# Rainbow.net
KiCad netlist of a schematic drawn in EasyEDA Pro
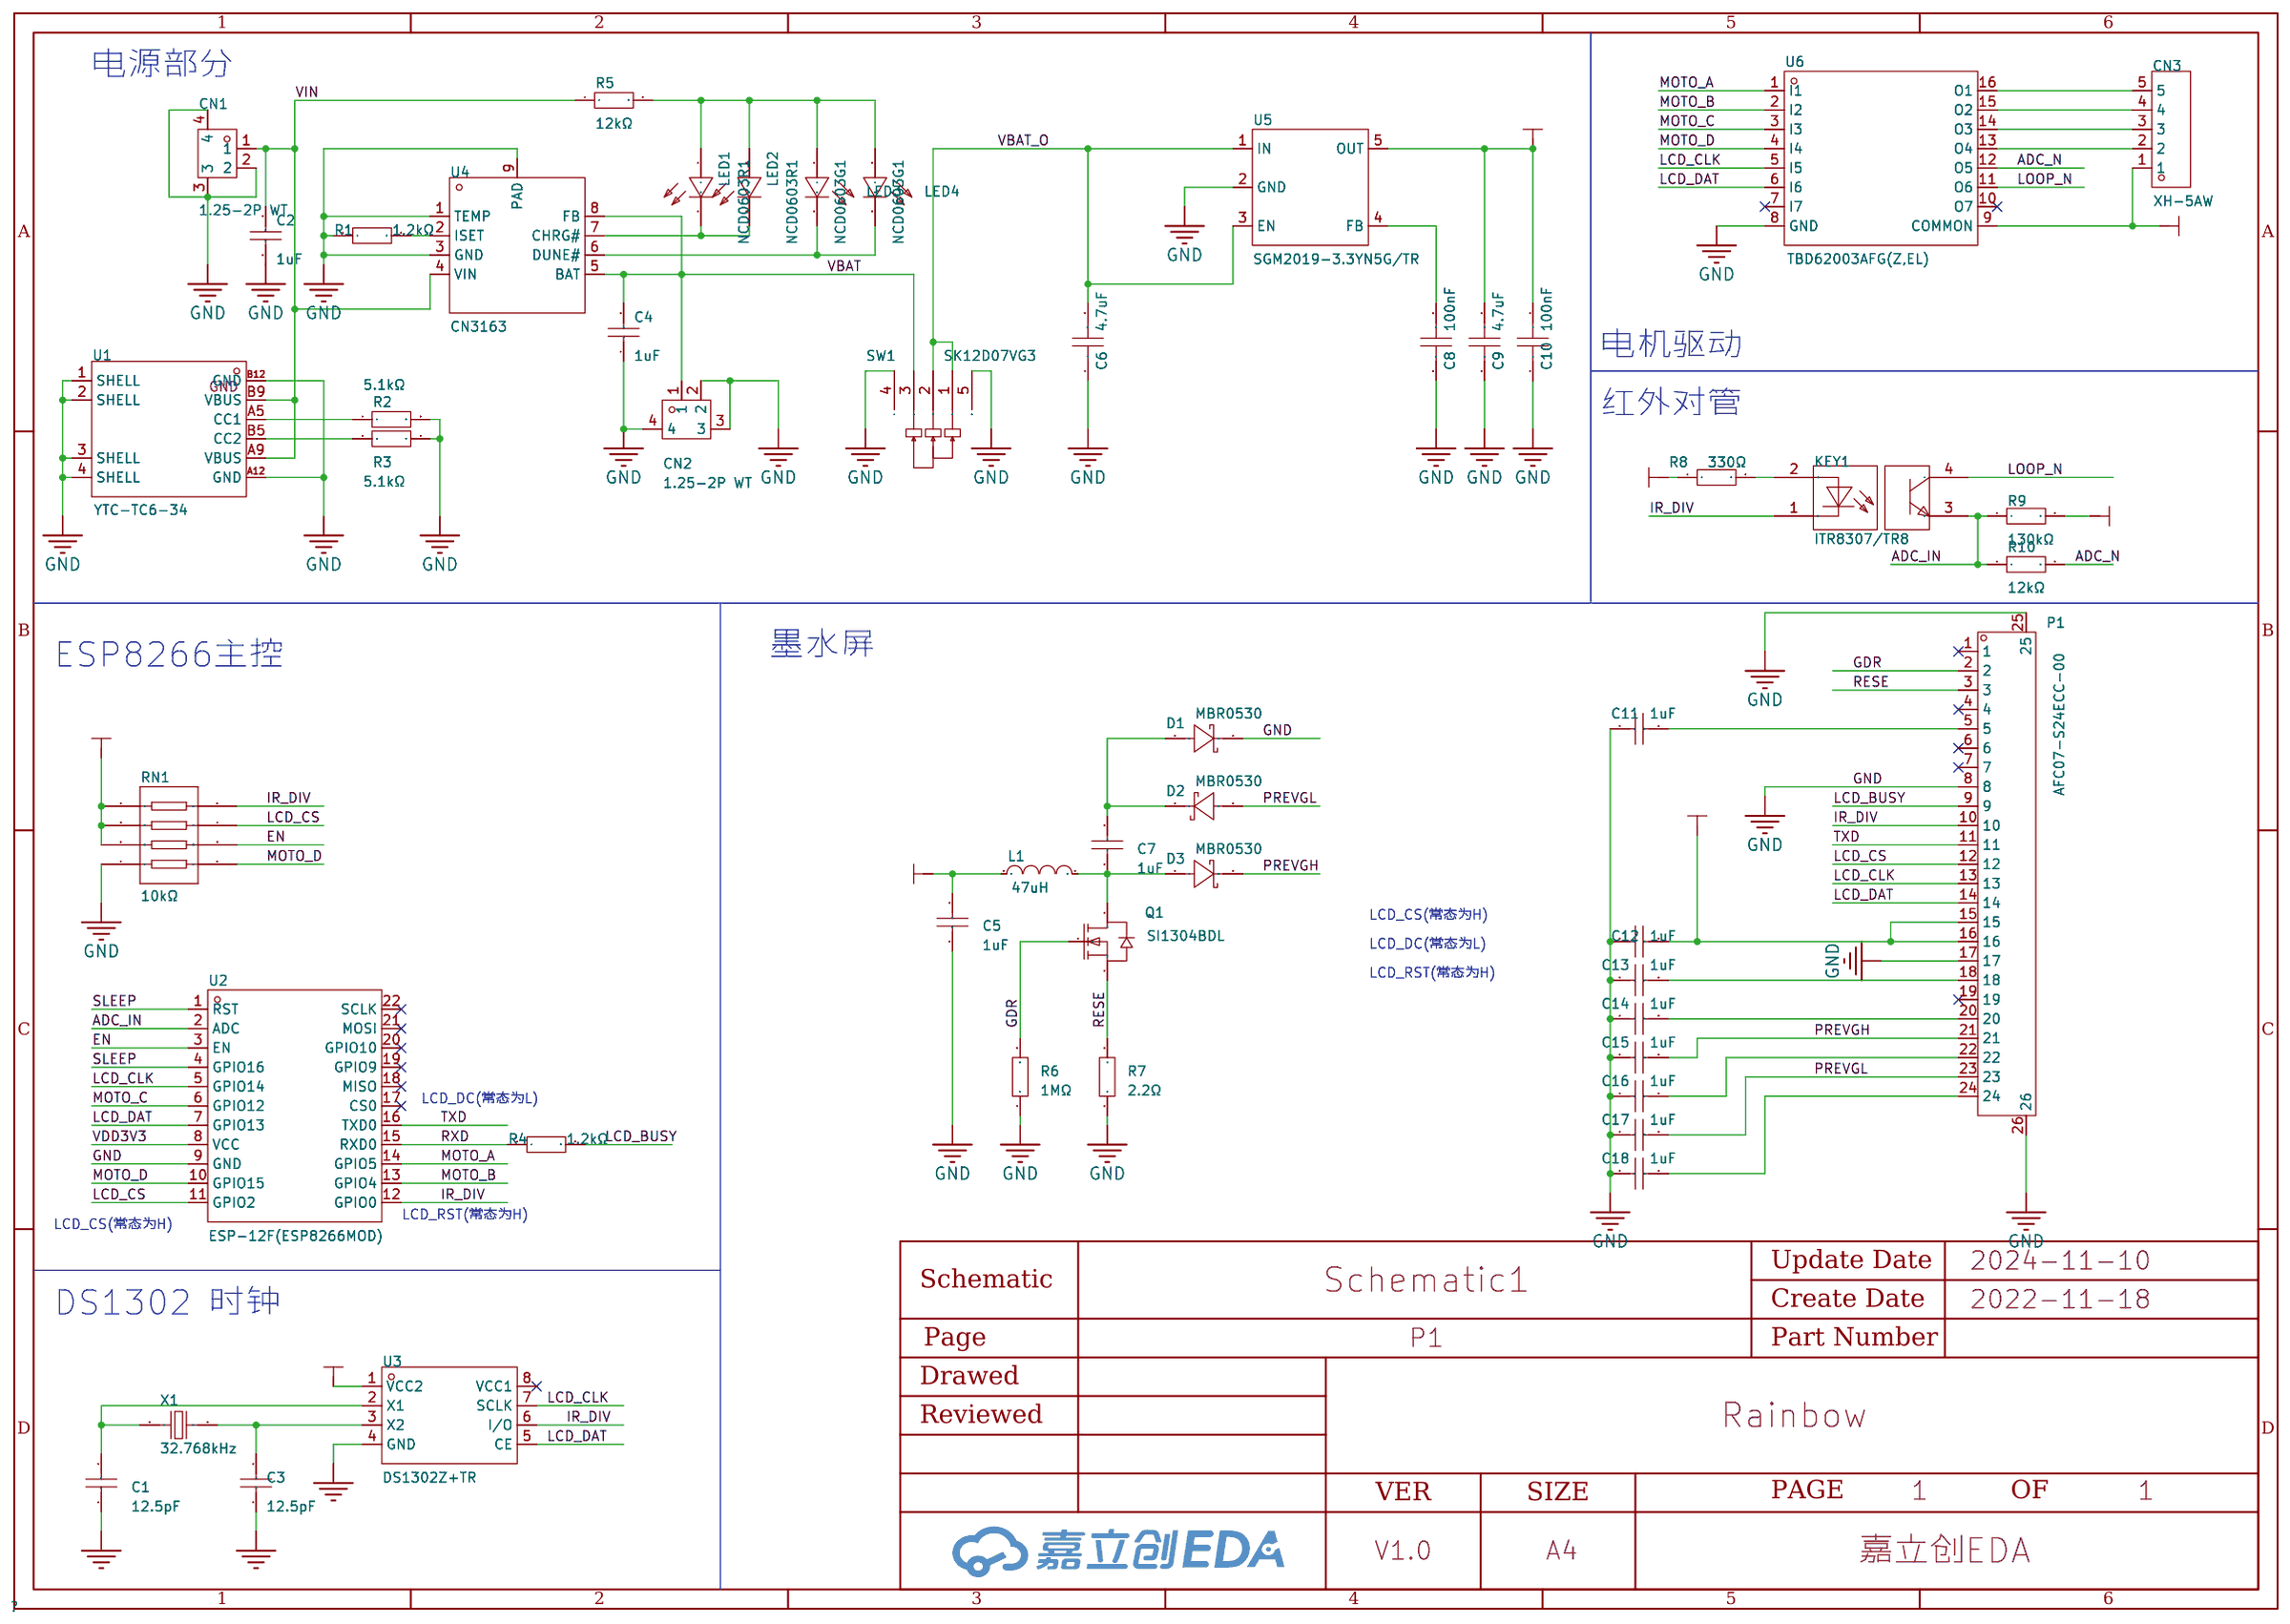
[diagram p0: schematic sheet]

(export (version "E")
  (design (tool "Eeschema 10.0.6"))
  (components
    (comp (ref "C1")
      (value "12.5pF")
      (footprint "easyedapro:C0603")
      (description "容值:20pF;精度:±5%;额定电压:50V;材质(温度系数):NP0;")
      (fields
        (field (name "Manufacturer Part") "CC0603JRNPO9BN200")
        (field (name "Manufacturer") "YAGEO(国巨)")
      )
      (libsource (lib "easyedapro") (part "CC0603JRNPO9BN200"))
    )
    (comp (ref "C2")
      (value "1uF")
      (footprint "easyedapro:C0603")
      (description "温度系数:X5R;精度:±10%;额定电压:50V;容值:1uF;")
      (fields
        (field (name "Manufacturer Part") "CL10A105KB8NNNC")
        (field (name "Manufacturer") "SAMSUNG(三星)")
      )
      (libsource (lib "easyedapro") (part "CL10A105KB8NNNC"))
    )
    (comp (ref "C3")
      (value "12.5pF")
      (footprint "easyedapro:C0603")
      (description "容值:20pF;精度:±5%;额定电压:50V;材质(温度系数):NP0;")
      (fields
        (field (name "Manufacturer Part") "CC0603JRNPO9BN200")
        (field (name "Manufacturer") "YAGEO(国巨)")
      )
      (libsource (lib "easyedapro") (part "CC0603JRNPO9BN200"))
    )
    (comp (ref "C4")
      (value "1uF")
      (footprint "easyedapro:C0603")
      (description "温度系数:X5R;精度:±10%;额定电压:50V;容值:1uF;")
      (fields
        (field (name "Manufacturer Part") "CL10A105KB8NNNC")
        (field (name "Manufacturer") "SAMSUNG(三星)")
      )
      (libsource (lib "easyedapro") (part "CL10A105KB8NNNC"))
    )
    (comp (ref "C5")
      (value "1uF")
      (footprint "easyedapro:C0603")
      (description "温度系数:X5R;精度:±10%;额定电压:50V;容值:1uF;")
      (fields
        (field (name "Manufacturer Part") "CL10A105KB8NNNC")
        (field (name "Manufacturer") "SAMSUNG(三星)")
      )
      (libsource (lib "easyedapro") (part "CL10A105KB8NNNC"))
    )
    (comp (ref "C6")
      (value "4.7uF")
      (footprint "easyedapro:C0603")
      (description "容值:10uF;精度:±10%;额定电压:10V;材质(温度系数):X5R;")
      (fields
        (field (name "Manufacturer Part") "CL10A106KP8NNNC")
        (field (name "Manufacturer") "SAMSUNG(三星)")
      )
      (libsource (lib "easyedapro") (part "CL10A106KP8NNNC"))
    )
    (comp (ref "C7")
      (value "1uF")
      (footprint "easyedapro:C0603")
      (description "温度系数:X5R;精度:±10%;额定电压:50V;容值:1uF;")
      (fields
        (field (name "Manufacturer Part") "CL10A105KB8NNNC")
        (field (name "Manufacturer") "SAMSUNG(三星)")
      )
      (libsource (lib "easyedapro") (part "CL10A105KB8NNNC"))
    )
    (comp (ref "C8")
      (value "100nF")
      (footprint "easyedapro:C0603")
      (description "容值:100nF;精度:±10%;额定电压:50V;材质(温度系数):X7R;")
      (fields
        (field (name "Manufacturer Part") "CC0603KRX7R9BB104")
        (field (name "Manufacturer") "YAGEO(国巨)")
      )
      (libsource (lib "easyedapro") (part "CC0603KRX7R9BB104"))
    )
    (comp (ref "C9")
      (value "4.7uF")
      (footprint "easyedapro:C0603")
      (description "容值:10uF;精度:±10%;额定电压:10V;材质(温度系数):X5R;")
      (fields
        (field (name "Manufacturer Part") "CL10A106KP8NNNC")
        (field (name "Manufacturer") "SAMSUNG(三星)")
      )
      (libsource (lib "easyedapro") (part "CL10A106KP8NNNC"))
    )
    (comp (ref "C10")
      (value "100nF")
      (footprint "easyedapro:C0603")
      (description "容值:100nF;精度:±10%;额定电压:50V;材质(温度系数):X7R;")
      (fields
        (field (name "Manufacturer Part") "CC0603KRX7R9BB104")
        (field (name "Manufacturer") "YAGEO(国巨)")
      )
      (libsource (lib "easyedapro") (part "CC0603KRX7R9BB104"))
    )
    (comp (ref "C11")
      (value "1uF")
      (footprint "easyedapro:C0603")
      (description "温度系数:X5R;精度:±10%;额定电压:50V;容值:1uF;")
      (fields
        (field (name "Manufacturer Part") "CL10A105KB8NNNC")
        (field (name "Manufacturer") "SAMSUNG(三星)")
      )
      (libsource (lib "easyedapro") (part "CL10A105KB8NNNC"))
    )
    (comp (ref "C12")
      (value "1uF")
      (footprint "easyedapro:C0603")
      (description "温度系数:X5R;精度:±10%;额定电压:50V;容值:1uF;")
      (fields
        (field (name "Manufacturer Part") "CL10A105KB8NNNC")
        (field (name "Manufacturer") "SAMSUNG(三星)")
      )
      (libsource (lib "easyedapro") (part "CL10A105KB8NNNC"))
    )
    (comp (ref "C13")
      (value "1uF")
      (footprint "easyedapro:C0603")
      (description "温度系数:X5R;精度:±10%;额定电压:50V;容值:1uF;")
      (fields
        (field (name "Manufacturer Part") "CL10A105KB8NNNC")
        (field (name "Manufacturer") "SAMSUNG(三星)")
      )
      (libsource (lib "easyedapro") (part "CL10A105KB8NNNC"))
    )
    (comp (ref "C14")
      (value "1uF")
      (footprint "easyedapro:C0603")
      (description "温度系数:X5R;精度:±10%;额定电压:50V;容值:1uF;")
      (fields
        (field (name "Manufacturer Part") "CL10A105KB8NNNC")
        (field (name "Manufacturer") "SAMSUNG(三星)")
      )
      (libsource (lib "easyedapro") (part "CL10A105KB8NNNC"))
    )
    (comp (ref "C15")
      (value "1uF")
      (footprint "easyedapro:C0603")
      (description "温度系数:X5R;精度:±10%;额定电压:50V;容值:1uF;")
      (fields
        (field (name "Manufacturer Part") "CL10A105KB8NNNC")
        (field (name "Manufacturer") "SAMSUNG(三星)")
      )
      (libsource (lib "easyedapro") (part "CL10A105KB8NNNC"))
    )
    (comp (ref "C16")
      (value "1uF")
      (footprint "easyedapro:C0603")
      (description "温度系数:X5R;精度:±10%;额定电压:50V;容值:1uF;")
      (fields
        (field (name "Manufacturer Part") "CL10A105KB8NNNC")
        (field (name "Manufacturer") "SAMSUNG(三星)")
      )
      (libsource (lib "easyedapro") (part "CL10A105KB8NNNC"))
    )
    (comp (ref "C17")
      (value "1uF")
      (footprint "easyedapro:C0603")
      (description "温度系数:X5R;精度:±10%;额定电压:50V;容值:1uF;")
      (fields
        (field (name "Manufacturer Part") "CL10A105KB8NNNC")
        (field (name "Manufacturer") "SAMSUNG(三星)")
      )
      (libsource (lib "easyedapro") (part "CL10A105KB8NNNC"))
    )
    (comp (ref "C18")
      (value "1uF")
      (footprint "easyedapro:C0603")
      (description "温度系数:X5R;精度:±10%;额定电压:50V;容值:1uF;")
      (fields
        (field (name "Manufacturer Part") "CL10A105KB8NNNC")
        (field (name "Manufacturer") "SAMSUNG(三星)")
      )
      (libsource (lib "easyedapro") (part "CL10A105KB8NNNC"))
    )
    (comp (ref "CN1")
      (value "1.25-2P WT")
      (footprint "easyedapro:CONN-SMD_1.25-2PWT")
      (description "参考系列:-;间距:1.25mm;插针结构:1x2P;排数:1;每排PIN数:2;行距:-;公母:公型插针;安装方式:卧贴;额定电流:1A;工作温度范围:-25~+85;")
      (fields (field (name "Manufacturer") "SHOU HAN(首韩)"))
      (libsource (lib "easyedapro") (part "1.25-2P WT"))
    )
    (comp (ref "CN2")
      (value "1.25-2P WT")
      (footprint "easyedapro:CONN-SMD_1.25-2PWT")
      (description "参考系列:-;间距:1.25mm;插针结构:1x2P;排数:1;每排PIN数:2;行距:-;公母:公型插针;安装方式:卧贴;额定电流:1A;工作温度范围:-25~+85;")
      (fields (field (name "Manufacturer") "SHOU HAN(首韩)"))
      (libsource (lib "easyedapro") (part "1.25-2P WT"))
    )
    (comp (ref "CN3")
      (value "XH-5AW")
      (footprint "easyedapro:CONN-TH_5P-P2.54_XH-5AW_C2908614")
      (description "参考系列:XH;间距:2.54mm;插针结构:1x5P;排数:1;每排PIN数:5;行距:-;公母:公型插针;安装方式:弯插;额定电流:3A;工作温度范围:-25~+85;")
      (fields (field (name "Manufacturer") "HCTL(华灿天禄)"))
      (libsource (lib "easyedapro") (part "XH-5AW_C2908614"))
    )
    (comp (ref "D1")
      (value "MBR0530")
      (footprint "easyedapro:SOD-123_L2.7-W1.6-LS3.7-RD-1")
      (description "直流反向耐压(Vr):30V;平均整流电流(Io):500mA;正向压降(Vf):550mV@500mA;")
      (fields (field (name "Manufacturer") "YANGJIE(扬杰)"))
      (libsource (lib "easyedapro") (part "MBR0530_C699108"))
    )
    (comp (ref "D2")
      (value "MBR0530")
      (footprint "easyedapro:SOD-123_L2.7-W1.6-LS3.7-RD-1")
      (description "直流反向耐压(Vr):30V;平均整流电流(Io):500mA;正向压降(Vf):550mV@500mA;")
      (fields (field (name "Manufacturer") "YANGJIE(扬杰)"))
      (libsource (lib "easyedapro") (part "MBR0530_C699108"))
    )
    (comp (ref "D3")
      (value "MBR0530")
      (footprint "easyedapro:SOD-123_L2.7-W1.6-LS3.7-RD-1")
      (description "直流反向耐压(Vr):30V;平均整流电流(Io):500mA;正向压降(Vf):550mV@500mA;")
      (fields (field (name "Manufacturer") "YANGJIE(扬杰)"))
      (libsource (lib "easyedapro") (part "MBR0530_C699108"))
    )
    (comp (ref "KEY1")
      (value "ITR8307/TR8")
      (footprint "easyedapro:OPTO-4P-L3.4-W2.7-P1.30-LS4.6")
      (fields (field (name "Manufacturer") "EVERLIGHT(台湾亿光)"))
      (libsource (lib "easyedapro") (part "ITR8307/TR8"))
    )
    (comp (ref "L1")
      (value "47uH")
      (footprint "easyedapro:IND-SMD_L5.0-W5.0_MPIT50X0")
      (description "电感值:47uH;精度:±20%;额定电流:-;直流电阻(DCR):-;")
      (fields
        (field (name "Manufacturer Part") "MPIT5020-470M-LF")
        (field (name "Manufacturer") "microgate(麦捷科技)")
      )
      (libsource (lib "easyedapro") (part "MPIT5020-470M-LF"))
    )
    (comp (ref "LED1")
      (value "NCD0603R1")
      (footprint "easyedapro:LED0603-RD_RED")
      (description "发光颜色:红灯;")
      (fields (field (name "Manufacturer") "国星光电"))
      (libsource (lib "easyedapro") (part "FC-DA1608HRK-620D"))
    )
    (comp (ref "LED2")
      (value "NCD0603R1")
      (footprint "easyedapro:LED0603-RD_RED")
      (description "发光颜色:红灯;")
      (fields (field (name "Manufacturer") "国星光电"))
      (libsource (lib "easyedapro") (part "FC-DA1608HRK-620D"))
    )
    (comp (ref "LED3")
      (value "NCD0603G1")
      (footprint "easyedapro:LED0603-RD")
      (description "发光颜色:翠绿;")
      (fields (field (name "Manufacturer") "国星光电"))
      (libsource (lib "easyedapro") (part "FC-D1608UGK-520D10"))
    )
    (comp (ref "LED4")
      (value "NCD0603G1")
      (footprint "easyedapro:LED0603-RD")
      (description "发光颜色:翠绿;")
      (fields (field (name "Manufacturer") "国星光电"))
      (libsource (lib "easyedapro") (part "FC-D1608UGK-520D10"))
    )
    (comp (ref "P1")
      (value "AFC07-S24ECC-00")
      (footprint "easyedapro:FPC-SMD_24P-L17.5-W5.4-P0.50")
      (description "间距:0.5mm;触点数量:24;锁定特性:抽屉式;安装类型:卧贴;触点类型:上接;")
      (fields (field (name "Manufacturer") "JS(钜硕电子)"))
      (libsource (lib "easyedapro") (part "FPC 0.5MM 24P Pull type H2.0mm Pick up"))
    )
    (comp (ref "Q1")
      (value "SI1304BDL")
      (footprint "easyedapro:SC-70-3_L2.1-W1.3-P1.30-LS2.1-TL")
      (fields (field (name "Manufacturer") "VBsemi(微碧)"))
      (libsource (lib "easyedapro") (part "SI1304BDL"))
    )
    (comp (ref "R1")
      (value "1.2kΩ")
      (footprint "easyedapro:R0603")
      (description "电阻类型:厚膜电阻;阻值:1.2kΩ;精度:±1%;功率:100mW;温度系数:±100ppm/;最大工作电压:75V;工作温度范围:-55~+155;")
      (fields (field (name "Manufacturer Part") "RC0603FR-071K2L") (field (name "Manufacturer") "YAGEO(国巨)"))
      (libsource (lib "easyedapro") (part "RC0603FR-071K2L"))
    )
    (comp (ref "R2")
      (value "5.1kΩ")
      (footprint "easyedapro:R0603")
      (description "电阻类型:厚膜电阻;阻值:12kΩ;精度:±1%;功率:100mW;温度系数:±100ppm/;最大工作电压:75V;工作温度范围:-55~+155;")
      (fields (field (name "Manufacturer Part") "RC0603FR-0712KL") (field (name "Manufacturer") "YAGEO(国巨)"))
      (libsource (lib "easyedapro") (part "RC0603FR-0712KL"))
    )
    (comp (ref "R3")
      (value "5.1kΩ")
      (footprint "easyedapro:R0603")
      (description "电阻类型:厚膜电阻;阻值:12kΩ;精度:±1%;功率:100mW;温度系数:±100ppm/;最大工作电压:75V;工作温度范围:-55~+155;")
      (fields (field (name "Manufacturer Part") "RC0603FR-0712KL") (field (name "Manufacturer") "YAGEO(国巨)"))
      (libsource (lib "easyedapro") (part "RC0603FR-0712KL"))
    )
    (comp (ref "R4")
      (value "1.2kΩ")
      (footprint "easyedapro:R0603")
      (description "电阻类型:厚膜电阻;阻值:1.2kΩ;精度:±1%;功率:100mW;温度系数:±100ppm/;最大工作电压:75V;工作温度范围:-55~+155;")
      (fields (field (name "Manufacturer Part") "RC0603FR-071K2L") (field (name "Manufacturer") "YAGEO(国巨)"))
      (libsource (lib "easyedapro") (part "RC0603FR-071K2L"))
    )
    (comp (ref "R5")
      (value "12kΩ")
      (footprint "easyedapro:R0603")
      (description "电阻类型:厚膜电阻;阻值:12kΩ;精度:±1%;功率:100mW;温度系数:±100ppm/;最大工作电压:75V;工作温度范围:-55~+155;")
      (fields (field (name "Manufacturer Part") "RC0603FR-0712KL") (field (name "Manufacturer") "YAGEO(国巨)"))
      (libsource (lib "easyedapro") (part "RC0603FR-0712KL"))
    )
    (comp (ref "R6")
      (value "1MΩ")
      (footprint "easyedapro:R0603")
      (description "电阻类型:厚膜电阻;阻值:1MΩ;精度:±1%;功率:100mW;温度系数:±100ppm/;最大工作电压:75V;工作温度范围:-55~+155;")
      (fields (field (name "Manufacturer Part") "RC0603FR-071ML") (field (name "Manufacturer") "YAGEO(国巨)"))
      (libsource (lib "easyedapro") (part "RC0603FR-071ML"))
    )
    (comp (ref "R7")
      (value "2.2Ω")
      (footprint "easyedapro:R0603")
      (description "电阻类型:厚膜电阻;阻值:2.2Ω;精度:±1%;功率:100mW;温度系数:±200ppm/;最大工作电压:75V;工作温度范围:-55~+155;")
      (fields (field (name "Manufacturer Part") "RC0603FR-072R2L") (field (name "Manufacturer") "YAGEO(国巨)"))
      (libsource (lib "easyedapro") (part "RC0603FR-072R2L"))
    )
    (comp (ref "R8")
      (value "330Ω")
      (footprint "easyedapro:R0603")
      (description "电阻类型:厚膜电阻;阻值:330Ω;精度:±1%;功率:100mW;温度系数:±100ppm/;最大工作电压:75V;工作温度范围:-55~+155;")
      (fields (field (name "Manufacturer Part") "RC0603FR-07330RL") (field (name "Manufacturer") "YAGEO(国巨)"))
      (libsource (lib "easyedapro") (part "RC0603FR-07330RL"))
    )
    (comp (ref "R9")
      (value "130kΩ")
      (footprint "easyedapro:R0603")
      (description "电阻类型:厚膜电阻;阻值:130kΩ;精度:±1%;功率:100mW;")
      (fields (field (name "Manufacturer Part") "RC0603FR-07130KL") (field (name "Manufacturer") "YAGEO(国巨)"))
      (libsource (lib "easyedapro") (part "RC0603FR-07130KL"))
    )
    (comp (ref "R10")
      (value "12kΩ")
      (footprint "easyedapro:R0603")
      (description "电阻类型:厚膜电阻;阻值:12kΩ;精度:±1%;功率:100mW;温度系数:±100ppm/;最大工作电压:75V;工作温度范围:-55~+155;")
      (fields (field (name "Manufacturer Part") "RC0603FR-0712KL") (field (name "Manufacturer") "YAGEO(国巨)"))
      (libsource (lib "easyedapro") (part "RC0603FR-0712KL"))
    )
    (comp (ref "RN1")
      (value "10kΩ")
      (footprint "easyedapro:RES-ARRAY-SMD_0603-8P-L3.2-W1.6-BL")
      (description "阻值:10kΩ;单个元件功率:62.5mW;电阻器数:4;引脚数:8;")
      (fields
        (field (name "Manufacturer Part") "4D03WGJ0103T5E")
        (field (name "Manufacturer") "UNI-ROYAL(厚声)")
      )
      (libsource (lib "easyedapro") (part "4D03WGJ0103T5E"))
    )
    (comp (ref "SW1")
      (value "SK12D07VG3")
      (footprint "easyedapro:SW-TH_SK12D07VG3")
      (fields (field (name "Manufacturer") "SHOU HAN(首韩)"))
      (libsource (lib "easyedapro") (part "SK12D07VG3_C431547"))
    )
    (comp (ref "U1")
      (value "YTC-TC6-34")
      (footprint "easyedapro:USB-C-SMD_YIYUAN_YTC-TC6-33")
      (description "连接器类型:Type-C;标准:-;公母:母座;触点数量:6;端口数量:1;安装方式:沉板;额定电流 - 电源:5A;工作温度范围:-20°C~+85°C;")
      (fields (field (name "Manufacturer") "YIYUAN(怡远)") (field (name "NAME") "GND"))
      (libsource (lib "easyedapro") (part "YTC-TC6-34"))
    )
    (comp (ref "U2")
      (value "ESP-12F(ESP8266MOD)")
      (footprint "easyedapro:WIFIM-SMD_ESP-12F-ESP8266MOD")
      (description "屏蔽罩上的丝印是：ESP8266MOD，ESP8266EX串口WIFI")
      (fields (field (name "Manufacturer") "Ai-Thinker(安信可)"))
      (libsource (lib "easyedapro") (part "ESP-12F(ESP8266MOD)"))
    )
    (comp (ref "U3")
      (value "DS1302Z+TR")
      (footprint "easyedapro:SOIC-8_L4.9-W3.9-P1.27-LS6.0-BL")
      (description "接口:SPI;")
      (fields (field (name "Manufacturer") "ADI(亚德诺)/MAXIM(美信)"))
      (libsource (lib "easyedapro") (part "DS1302ZN+"))
    )
    (comp (ref "U4")
      (value "CN3163")
      (footprint "easyedapro:ESOP-8_L4.9-W3.9-P1.27-LS6.0-BL-EP")
      (description "充电电池的类型:-;电池单元组数:-;最大充电电流:-;充满的电池组电压:-;最大供应电压:-;")
      (fields (field (name "Manufacturer") "CONSONANCE(上海如韵)"))
      (libsource (lib "easyedapro") (part "CN3163"))
    )
    (comp (ref "U5")
      (value "SGM2019-3.3YN5G/TR")
      (footprint "easyedapro:SOT-23-5_L3.0-W1.7-P0.95-LS2.8-BR")
      (fields (field (name "Manufacturer") "SGMICRO(圣邦微)"))
      (libsource (lib "easyedapro") (part "SGM2019-3.3YN5G"))
    )
    (comp (ref "U6")
      (value "TBD62003AFG(Z,EL)")
      (footprint "easyedapro:SOIC-16_L10.8-W4.5-P1.27-LS6.8-BL")
      (description "新产品，本芯片用场效应管作输出管，相比传统的ULN2003（三极管做输出管）管压降更低，芯片发热更少，驱动性能更佳。")
      (fields (field (name "Manufacturer") "TOSHIBA(东芝)"))
      (libsource (lib "easyedapro") (part "TBD62003AFG,EL"))
    )
    (comp (ref "X1")
      (value "32.768kHz")
      (footprint "easyedapro:CRYSTAL-SMD_L7.0-W3.2-LS7.5")
      (description "频率:32.768kHz;常温频差:±20ppm;外接负载电容:12.5pF;频率稳定度(全温):±10ppm;")
      (fields
        (field (name "Manufacturer Part") "HY32768KSMD3068YA2R30")
        (field (name "Manufacturer") "Huiyuan crystal(惠源晶工)")
      )
      (libsource (lib "easyedapro") (part "HY32768KSMD3068YA2R30"))
    )
  )
  (nets
    (net (code "1") (name "/ADC_IN") (class "Default")
      (node (ref "KEY1") (pin "3") (pinfunction "3_3") (pintype "input"))
      (node (ref "R10") (pin "1") (pinfunction "1_1") (pintype "input"))
      (node (ref "R9") (pin "1") (pinfunction "1_1") (pintype "input"))
      (node (ref "U2") (pin "2") (pinfunction "ADC_2") (pintype "input"))
    )
    (net (code "2") (name "/ADC_N") (class "Default")
      (node (ref "R10") (pin "2") (pinfunction "2_2") (pintype "input"))
      (node (ref "U6") (pin "12") (pinfunction "O5_12") (pintype "input"))
    )
    (net (code "3") (name "/EN") (class "Default")
      (node (ref "RN1") (pin "6") (pinfunction "6_6") (pintype "input"))
      (node (ref "U2") (pin "3") (pinfunction "EN_3") (pintype "input"))
    )
    (net (code "4") (name "/GDR") (class "Default")
      (node (ref "P1") (pin "2") (pinfunction "2_2") (pintype "input"))
      (node (ref "Q1") (pin "1") (pinfunction "G_1") (pintype "input"))
      (node (ref "R6") (pin "2") (pinfunction "2_2") (pintype "input"))
    )
    (net (code "5") (name "/IR_DIV") (class "Default")
      (node (ref "KEY1") (pin "1") (pinfunction "1_1") (pintype "input"))
      (node (ref "P1") (pin "10") (pinfunction "10_10") (pintype "input"))
      (node (ref "RN1") (pin "8") (pinfunction "8_8") (pintype "input"))
      (node (ref "U2") (pin "12") (pinfunction "GPIO0_12") (pintype "input"))
      (node (ref "U3") (pin "6") (pinfunction "I/O_6") (pintype "input"))
    )
    (net (code "6") (name "/LCD_BUSY") (class "Default")
      (node (ref "P1") (pin "9") (pinfunction "9_9") (pintype "input"))
      (node (ref "R4") (pin "2") (pinfunction "2_2") (pintype "input"))
    )
    (net (code "7") (name "/LCD_CLK") (class "Default")
      (node (ref "P1") (pin "13") (pinfunction "13_13") (pintype "input"))
      (node (ref "U2") (pin "5") (pinfunction "GPIO14_5") (pintype "input"))
      (node (ref "U3") (pin "7") (pinfunction "SCLK_7") (pintype "input"))
      (node (ref "U6") (pin "5") (pinfunction "I5_5") (pintype "input"))
    )
    (net (code "8") (name "/LCD_CS") (class "Default")
      (node (ref "P1") (pin "12") (pinfunction "12_12") (pintype "input"))
      (node (ref "RN1") (pin "7") (pinfunction "7_7") (pintype "input"))
      (node (ref "U2") (pin "11") (pinfunction "GPIO2_11") (pintype "input"))
    )
    (net (code "9") (name "/LCD_DAT") (class "Default")
      (node (ref "P1") (pin "14") (pinfunction "14_14") (pintype "input"))
      (node (ref "U2") (pin "7") (pinfunction "GPIO13_7") (pintype "input"))
      (node (ref "U3") (pin "5") (pinfunction "CE_5") (pintype "input"))
      (node (ref "U6") (pin "6") (pinfunction "I6_6") (pintype "input"))
    )
    (net (code "10") (name "/LOOP_N") (class "Default")
      (node (ref "KEY1") (pin "4") (pinfunction "4_4") (pintype "input"))
      (node (ref "U6") (pin "11") (pinfunction "O6_11") (pintype "input"))
    )
    (net (code "11") (name "/MOTO_A") (class "Default")
      (node (ref "U2") (pin "14") (pinfunction "GPIO5_14") (pintype "input"))
      (node (ref "U6") (pin "1") (pinfunction "I1_1") (pintype "input"))
    )
    (net (code "12") (name "/MOTO_B") (class "Default")
      (node (ref "U2") (pin "13") (pinfunction "GPIO4_13") (pintype "input"))
      (node (ref "U6") (pin "2") (pinfunction "I2_2") (pintype "input"))
    )
    (net (code "13") (name "/MOTO_C") (class "Default")
      (node (ref "U2") (pin "6") (pinfunction "GPIO12_6") (pintype "input"))
      (node (ref "U6") (pin "3") (pinfunction "I3_3") (pintype "input"))
    )
    (net (code "14") (name "/MOTO_D") (class "Default")
      (node (ref "RN1") (pin "5") (pinfunction "5_5") (pintype "input"))
      (node (ref "U2") (pin "10") (pinfunction "GPIO15_10") (pintype "input"))
      (node (ref "U6") (pin "4") (pinfunction "I4_4") (pintype "input"))
    )
    (net (code "15") (name "/PREVGH") (class "Default")
      (node (ref "C15") (pin "2") (pinfunction "2_2") (pintype "input"))
      (node (ref "D3") (pin "1") (pinfunction "K_1") (pintype "input"))
      (node (ref "P1") (pin "21") (pinfunction "21_21") (pintype "input"))
    )
    (net (code "16") (name "/PREVGL") (class "Default")
      (node (ref "C17") (pin "2") (pinfunction "2_2") (pintype "input"))
      (node (ref "D2") (pin "2") (pinfunction "A_2") (pintype "input"))
      (node (ref "P1") (pin "23") (pinfunction "23_23") (pintype "input"))
    )
    (net (code "17") (name "/RESE") (class "Default")
      (node (ref "P1") (pin "3") (pinfunction "3_3") (pintype "input"))
      (node (ref "Q1") (pin "2") (pinfunction "S_2") (pintype "input"))
      (node (ref "R7") (pin "2") (pinfunction "2_2") (pintype "input"))
    )
    (net (code "18") (name "/RXD") (class "Default")
      (node (ref "R4") (pin "1") (pinfunction "1_1") (pintype "input"))
      (node (ref "U2") (pin "15") (pinfunction "RXD0_15") (pintype "input"))
    )
    (net (code "19") (name "/SLEEP") (class "Default")
      (node (ref "U2") (pin "1") (pinfunction "RST_1") (pintype "input"))
      (node (ref "U2") (pin "4") (pinfunction "GPIO16_4") (pintype "input"))
    )
    (net (code "20") (name "/TXD") (class "Default")
      (node (ref "P1") (pin "11") (pinfunction "11_11") (pintype "input"))
      (node (ref "U2") (pin "16") (pinfunction "TXD0_16") (pintype "input"))
    )
    (net (code "21") (name "/VBAT") (class "Default")
      (node (ref "C4") (pin "2") (pinfunction "2_2") (pintype "input"))
      (node (ref "CN2") (pin "1") (pinfunction "1_1") (pintype "input"))
      (node (ref "SW1") (pin "3") (pinfunction "3_3") (pintype "input"))
      (node (ref "U4") (pin "5") (pinfunction "BAT_5") (pintype "input"))
      (node (ref "U4") (pin "8") (pinfunction "FB_8") (pintype "input"))
    )
    (net (code "22") (name "/VIN") (class "Default")
      (node (ref "C2") (pin "2") (pinfunction "2_2") (pintype "input"))
      (node (ref "CN1") (pin "1") (pinfunction "1_1") (pintype "input"))
      (node (ref "R5") (pin "1") (pinfunction "1_1") (pintype "input"))
      (node (ref "U1") (pin "A9") (pinfunction "VBUS_A9") (pintype "unspecified"))
      (node (ref "U1") (pin "B9") (pinfunction "VBUS_B9") (pintype "unspecified"))
      (node (ref "U4") (pin "4") (pinfunction "VIN_4") (pintype "input"))
    )
    (net (code "23") (name "GND") (class "Default")
      (node (ref "C1") (pin "1") (pinfunction "1_1") (pintype "input"))
      (node (ref "C10") (pin "1") (pinfunction "1_1") (pintype "input"))
      (node (ref "C11") (pin "1") (pinfunction "1_1") (pintype "input"))
      (node (ref "C12") (pin "1") (pinfunction "1_1") (pintype "input"))
      (node (ref "C13") (pin "1") (pinfunction "1_1") (pintype "input"))
      (node (ref "C14") (pin "1") (pinfunction "1_1") (pintype "input"))
      (node (ref "C15") (pin "1") (pinfunction "1_1") (pintype "input"))
      (node (ref "C16") (pin "1") (pinfunction "1_1") (pintype "input"))
      (node (ref "C17") (pin "1") (pinfunction "1_1") (pintype "input"))
      (node (ref "C18") (pin "1") (pinfunction "1_1") (pintype "input"))
      (node (ref "C2") (pin "1") (pinfunction "1_1") (pintype "input"))
      (node (ref "C3") (pin "1") (pinfunction "1_1") (pintype "input"))
      (node (ref "C4") (pin "1") (pinfunction "1_1") (pintype "input"))
      (node (ref "C5") (pin "1") (pinfunction "1_1") (pintype "input"))
      (node (ref "C6") (pin "1") (pinfunction "1_1") (pintype "input"))
      (node (ref "C8") (pin "1") (pinfunction "1_1") (pintype "input"))
      (node (ref "C9") (pin "1") (pinfunction "1_1") (pintype "input"))
      (node (ref "CN1") (pin "2") (pinfunction "2_2") (pintype "input"))
      (node (ref "CN1") (pin "3") (pinfunction "3_3") (pintype "input"))
      (node (ref "CN1") (pin "4") (pinfunction "4_4") (pintype "input"))
      (node (ref "CN2") (pin "2") (pinfunction "2_2") (pintype "input"))
      (node (ref "CN2") (pin "3") (pinfunction "3_3") (pintype "input"))
      (node (ref "CN2") (pin "4") (pinfunction "4_4") (pintype "input"))
      (node (ref "D1") (pin "1") (pinfunction "K_1") (pintype "input"))
      (node (ref "P1") (pin "17") (pinfunction "17_17") (pintype "input"))
      (node (ref "P1") (pin "25") (pinfunction "25_25") (pintype "input"))
      (node (ref "P1") (pin "26") (pinfunction "26_26") (pintype "input"))
      (node (ref "P1") (pin "8") (pinfunction "8_8") (pintype "input"))
      (node (ref "R1") (pin "1") (pinfunction "1_1") (pintype "input"))
      (node (ref "R2") (pin "2") (pinfunction "2_2") (pintype "input"))
      (node (ref "R3") (pin "2") (pinfunction "2_2") (pintype "input"))
      (node (ref "R6") (pin "1") (pinfunction "1_1") (pintype "input"))
      (node (ref "R7") (pin "1") (pinfunction "1_1") (pintype "input"))
      (node (ref "RN1") (pin "4") (pinfunction "4_4") (pintype "input"))
      (node (ref "SW1") (pin "4") (pinfunction "4_4") (pintype "input"))
      (node (ref "SW1") (pin "5") (pinfunction "5_5") (pintype "input"))
      (node (ref "U1") (pin "1") (pinfunction "SHELL_1") (pintype "unspecified"))
      (node (ref "U1") (pin "2") (pinfunction "SHELL_2") (pintype "unspecified"))
      (node (ref "U1") (pin "3") (pinfunction "SHELL_3") (pintype "unspecified"))
      (node (ref "U1") (pin "4") (pinfunction "SHELL_4") (pintype "unspecified"))
      (node (ref "U1") (pin "A12") (pinfunction "GND_A12") (pintype "unspecified"))
      (node (ref "U1") (pin "B12") (pinfunction "GND_B12") (pintype "unspecified"))
      (node (ref "U2") (pin "9") (pinfunction "GND_9") (pintype "input"))
      (node (ref "U3") (pin "4") (pinfunction "GND_4") (pintype "input"))
      (node (ref "U4") (pin "1") (pinfunction "TEMP_1") (pintype "input"))
      (node (ref "U4") (pin "3") (pinfunction "GND_3") (pintype "input"))
      (node (ref "U4") (pin "9") (pinfunction "PAD_9") (pintype "input"))
      (node (ref "U5") (pin "2") (pinfunction "GND_2") (pintype "input"))
      (node (ref "U6") (pin "8") (pinfunction "GND_8") (pintype "input"))
    )
    (net (code "24") (name "Net-(C11-Pad2)") (class "Default")
      (node (ref "C11") (pin "2") (pinfunction "2_2") (pintype "input"))
      (node (ref "P1") (pin "5") (pinfunction "5_5") (pintype "input"))
    )
    (net (code "25") (name "Net-(C13-Pad2)") (class "Default")
      (node (ref "C13") (pin "2") (pinfunction "2_2") (pintype "input"))
      (node (ref "P1") (pin "18") (pinfunction "18_18") (pintype "input"))
    )
    (net (code "26") (name "Net-(C14-Pad2)") (class "Default")
      (node (ref "C14") (pin "2") (pinfunction "2_2") (pintype "input"))
      (node (ref "P1") (pin "20") (pinfunction "20_20") (pintype "input"))
    )
    (net (code "27") (name "Net-(C16-Pad2)") (class "Default")
      (node (ref "C16") (pin "2") (pinfunction "2_2") (pintype "input"))
      (node (ref "P1") (pin "22") (pinfunction "22_22") (pintype "input"))
    )
    (net (code "28") (name "Net-(C18-Pad2)") (class "Default")
      (node (ref "C18") (pin "2") (pinfunction "2_2") (pintype "input"))
      (node (ref "P1") (pin "24") (pinfunction "24_24") (pintype "input"))
    )
    (net (code "29") (name "Net-(D1-A)") (class "Default")
      (node (ref "C7") (pin "2") (pinfunction "2_2") (pintype "input"))
      (node (ref "D1") (pin "2") (pinfunction "A_2") (pintype "input"))
      (node (ref "D2") (pin "1") (pinfunction "K_1") (pintype "input"))
    )
    (net (code "30") (name "Net-(D3-A)") (class "Default")
      (node (ref "C7") (pin "1") (pinfunction "1_1") (pintype "input"))
      (node (ref "D3") (pin "2") (pinfunction "A_2") (pintype "input"))
      (node (ref "L1") (pin "2") (pinfunction "2_2") (pintype "input"))
      (node (ref "Q1") (pin "3") (pinfunction "D_3") (pintype "input"))
    )
    (net (code "31") (name "Net-(KEY1-Pad2)") (class "Default")
      (node (ref "KEY1") (pin "2") (pinfunction "2_2") (pintype "input"))
      (node (ref "R8") (pin "2") (pinfunction "2_2") (pintype "input"))
    )
    (net (code "32") (name "Net-(LED1-A)") (class "Default")
      (node (ref "LED1") (pin "2") (pinfunction "A_2") (pintype "input"))
      (node (ref "LED2") (pin "2") (pinfunction "A_2") (pintype "input"))
      (node (ref "LED3") (pin "2") (pinfunction "A_2") (pintype "input"))
      (node (ref "LED4") (pin "2") (pinfunction "A_2") (pintype "input"))
      (node (ref "R5") (pin "2") (pinfunction "2_2") (pintype "input"))
    )
    (net (code "33") (name "Net-(LED1-K)") (class "Default")
      (node (ref "LED1") (pin "1") (pinfunction "K_1") (pintype "input"))
      (node (ref "LED2") (pin "1") (pinfunction "K_1") (pintype "input"))
      (node (ref "U4") (pin "7") (pinfunction "CHRG#_7") (pintype "input"))
    )
    (net (code "34") (name "Net-(LED3-K)") (class "Default")
      (node (ref "LED3") (pin "1") (pinfunction "K_1") (pintype "input"))
      (node (ref "LED4") (pin "1") (pinfunction "K_1") (pintype "input"))
      (node (ref "U4") (pin "6") (pinfunction "DUNE#_6") (pintype "input"))
    )
    (net (code "35") (name "Net-(U1-CC1)") (class "Default")
      (node (ref "R2") (pin "1") (pinfunction "1_1") (pintype "input"))
      (node (ref "U1") (pin "A5") (pinfunction "CC1_A5") (pintype "unspecified"))
    )
    (net (code "36") (name "Net-(U1-CC2)") (class "Default")
      (node (ref "R3") (pin "1") (pinfunction "1_1") (pintype "input"))
      (node (ref "U1") (pin "B5") (pinfunction "CC2_B5") (pintype "unspecified"))
    )
    (net (code "37") (name "Net-(U3-X1)") (class "Default")
      (node (ref "C1") (pin "2") (pinfunction "2_2") (pintype "input"))
      (node (ref "U3") (pin "2") (pinfunction "X1_2") (pintype "input"))
      (node (ref "X1") (pin "1") (pinfunction "1_1") (pintype "unspecified"))
    )
    (net (code "38") (name "Net-(U3-X2)") (class "Default")
      (node (ref "C3") (pin "2") (pinfunction "2_2") (pintype "input"))
      (node (ref "U3") (pin "3") (pinfunction "X2_3") (pintype "input"))
      (node (ref "X1") (pin "2") (pinfunction "2_2") (pintype "unspecified"))
    )
    (net (code "39") (name "Net-(U4-ISET)") (class "Default")
      (node (ref "R1") (pin "2") (pinfunction "2_2") (pintype "input"))
      (node (ref "U4") (pin "2") (pinfunction "ISET_2") (pintype "input"))
    )
    (net (code "40") (name "Net-(U5-FB)") (class "Default")
      (node (ref "C8") (pin "2") (pinfunction "2_2") (pintype "input"))
      (node (ref "U5") (pin "4") (pinfunction "FB_4") (pintype "input"))
    )
    (net (code "41") (name "Net-(U6-O1)") (class "Default")
      (node (ref "CN3") (pin "5") (pinfunction "5_5") (pintype "input"))
      (node (ref "U6") (pin "16") (pinfunction "O1_16") (pintype "input"))
    )
    (net (code "42") (name "Net-(U6-O2)") (class "Default")
      (node (ref "CN3") (pin "4") (pinfunction "4_4") (pintype "input"))
      (node (ref "U6") (pin "15") (pinfunction "O2_15") (pintype "input"))
    )
    (net (code "43") (name "Net-(U6-O3)") (class "Default")
      (node (ref "CN3") (pin "3") (pinfunction "3_3") (pintype "input"))
      (node (ref "U6") (pin "14") (pinfunction "O3_14") (pintype "input"))
    )
    (net (code "44") (name "Net-(U6-O4)") (class "Default")
      (node (ref "CN3") (pin "2") (pinfunction "2_2") (pintype "input"))
      (node (ref "U6") (pin "13") (pinfunction "O4_13") (pintype "input"))
    )
    (net (code "45") (name "VBAT_O") (class "Default")
      (node (ref "C6") (pin "2") (pinfunction "2_2") (pintype "input"))
      (node (ref "CN3") (pin "1") (pinfunction "1_1") (pintype "input"))
      (node (ref "R9") (pin "2") (pinfunction "2_2") (pintype "input"))
      (node (ref "SW1") (pin "1") (pinfunction "1_1") (pintype "input"))
      (node (ref "SW1") (pin "2") (pinfunction "2_2") (pintype "input"))
      (node (ref "U5") (pin "1") (pinfunction "IN_1") (pintype "input"))
      (node (ref "U5") (pin "3") (pinfunction "EN_3") (pintype "input"))
      (node (ref "U6") (pin "9") (pinfunction "COMMON_9") (pintype "input"))
    )
    (net (code "46") (name "VDD3V3") (class "Default")
      (node (ref "C10") (pin "2") (pinfunction "2_2") (pintype "input"))
      (node (ref "C12") (pin "2") (pinfunction "2_2") (pintype "input"))
      (node (ref "C5") (pin "2") (pinfunction "2_2") (pintype "input"))
      (node (ref "C9") (pin "2") (pinfunction "2_2") (pintype "input"))
      (node (ref "L1") (pin "1") (pinfunction "1_1") (pintype "input"))
      (node (ref "P1") (pin "15") (pinfunction "15_15") (pintype "input"))
      (node (ref "P1") (pin "16") (pinfunction "16_16") (pintype "input"))
      (node (ref "R8") (pin "1") (pinfunction "1_1") (pintype "input"))
      (node (ref "RN1") (pin "1") (pinfunction "1_1") (pintype "input"))
      (node (ref "RN1") (pin "2") (pinfunction "2_2") (pintype "input"))
      (node (ref "RN1") (pin "3") (pinfunction "3_3") (pintype "input"))
      (node (ref "U2") (pin "8") (pinfunction "VCC_8") (pintype "input"))
      (node (ref "U3") (pin "1") (pinfunction "VCC2_1") (pintype "input"))
      (node (ref "U5") (pin "5") (pinfunction "OUT_5") (pintype "input"))
    )
    (net (code "47") (name "unconnected-(P1-Pad1)") (class "Default")
      (node (ref "P1") (pin "1") (pinfunction "1_1") (pintype "input+no_connect"))
    )
    (net (code "48") (name "unconnected-(P1-Pad4)") (class "Default")
      (node (ref "P1") (pin "4") (pinfunction "4_4") (pintype "input+no_connect"))
    )
    (net (code "49") (name "unconnected-(P1-Pad6)") (class "Default")
      (node (ref "P1") (pin "6") (pinfunction "6_6") (pintype "input+no_connect"))
    )
    (net (code "50") (name "unconnected-(P1-Pad7)") (class "Default")
      (node (ref "P1") (pin "7") (pinfunction "7_7") (pintype "input+no_connect"))
    )
    (net (code "51") (name "unconnected-(P1-Pad19)") (class "Default")
      (node (ref "P1") (pin "19") (pinfunction "19_19") (pintype "input+no_connect"))
    )
    (net (code "52") (name "unconnected-(U2-CS0-Pad17)") (class "Default")
      (node (ref "U2") (pin "17") (pinfunction "CS0_17") (pintype "input+no_connect"))
    )
    (net (code "53") (name "unconnected-(U2-GPIO9-Pad19)") (class "Default")
      (node (ref "U2") (pin "19") (pinfunction "GPIO9_19") (pintype "input+no_connect"))
    )
    (net (code "54") (name "unconnected-(U2-GPIO10-Pad20)") (class "Default")
      (node (ref "U2") (pin "20") (pinfunction "GPIO10_20") (pintype "input+no_connect"))
    )
    (net (code "55") (name "unconnected-(U2-MISO-Pad18)") (class "Default")
      (node (ref "U2") (pin "18") (pinfunction "MISO_18") (pintype "input+no_connect"))
    )
    (net (code "56") (name "unconnected-(U2-MOSI-Pad21)") (class "Default")
      (node (ref "U2") (pin "21") (pinfunction "MOSI_21") (pintype "input+no_connect"))
    )
    (net (code "57") (name "unconnected-(U2-SCLK-Pad22)") (class "Default")
      (node (ref "U2") (pin "22") (pinfunction "SCLK_22") (pintype "input+no_connect"))
    )
    (net (code "58") (name "unconnected-(U3-VCC1-Pad8)") (class "Default")
      (node (ref "U3") (pin "8") (pinfunction "VCC1_8") (pintype "input+no_connect"))
    )
    (net (code "59") (name "unconnected-(U6-I7-Pad7)") (class "Default")
      (node (ref "U6") (pin "7") (pinfunction "I7_7") (pintype "input+no_connect"))
    )
    (net (code "60") (name "unconnected-(U6-O7-Pad10)") (class "Default")
      (node (ref "U6") (pin "10") (pinfunction "O7_10") (pintype "input+no_connect"))
    )
  )
)
